# Multi-Channel-Thermocouple-Shield.net
KiCad netlist of a schematic drawn in EAGLE
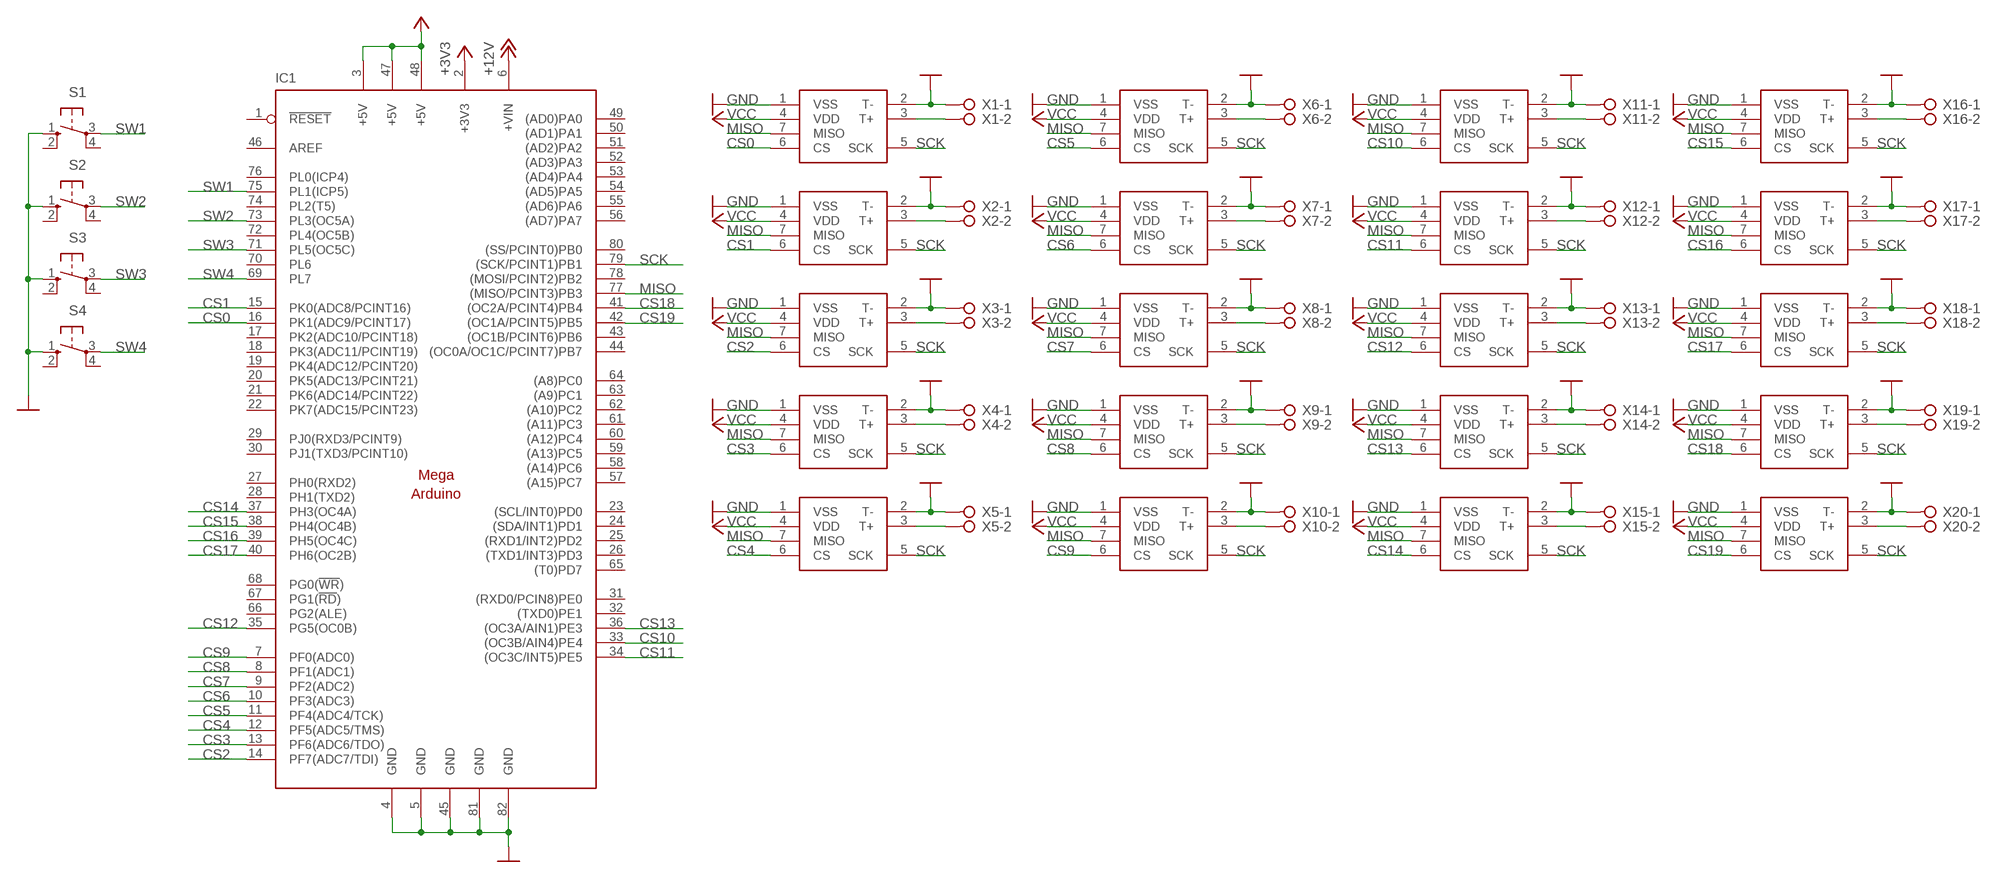
[diagram p0: schematic, sheet 1]

(export (version "E")
  (design (tool "Eeschema 10.0.6"))
  (components
    (comp (ref "IC1")
      (value "ARDUINO_MEGA-SHIELD")
      (footprint "eagle-import:MEGA_ARDUINO")
      (libsource (lib "eagle-import") (part "ARDUINO_MEGA-SHIELD"))
    )
    (comp (ref "S1")
      (value "SW-PUSHBUTTON")
      (footprint "eagle-import:B3F-10XX")
      (fields (field (name "MPN") "B3F-1000"))
      (libsource (lib "eagle-import") (part "SW-PUSHBUTTON"))
    )
    (comp (ref "S2")
      (value "SW-PUSHBUTTON")
      (footprint "eagle-import:B3F-10XX")
      (fields (field (name "MPN") "B3F-1000"))
      (libsource (lib "eagle-import") (part "SW-PUSHBUTTON"))
    )
    (comp (ref "S3")
      (value "SW-PUSHBUTTON")
      (footprint "eagle-import:B3F-10XX")
      (fields (field (name "MPN") "B3F-1000"))
      (libsource (lib "eagle-import") (part "SW-PUSHBUTTON"))
    )
    (comp (ref "S4")
      (value "SW-PUSHBUTTON")
      (footprint "eagle-import:B3F-10XX")
      (fields (field (name "MPN") "B3F-1000"))
      (libsource (lib "eagle-import") (part "SW-PUSHBUTTON"))
    )
    (comp (ref "U$1")
      (value "MAX6675")
      (footprint "eagle-import:SO08")
      (libsource (lib "eagle-import") (part "MAX6675"))
    )
    (comp (ref "U$2")
      (value "MAX6675")
      (footprint "eagle-import:SO08")
      (libsource (lib "eagle-import") (part "MAX6675"))
    )
    (comp (ref "U$3")
      (value "MAX6675")
      (footprint "eagle-import:SO08")
      (libsource (lib "eagle-import") (part "MAX6675"))
    )
    (comp (ref "U$4")
      (value "MAX6675")
      (footprint "eagle-import:SO08")
      (libsource (lib "eagle-import") (part "MAX6675"))
    )
    (comp (ref "U$5")
      (value "MAX6675")
      (footprint "eagle-import:SO08")
      (libsource (lib "eagle-import") (part "MAX6675"))
    )
    (comp (ref "U$6")
      (value "MAX6675")
      (footprint "eagle-import:SO08")
      (libsource (lib "eagle-import") (part "MAX6675"))
    )
    (comp (ref "U$7")
      (value "MAX6675")
      (footprint "eagle-import:SO08")
      (libsource (lib "eagle-import") (part "MAX6675"))
    )
    (comp (ref "U$8")
      (value "MAX6675")
      (footprint "eagle-import:SO08")
      (libsource (lib "eagle-import") (part "MAX6675"))
    )
    (comp (ref "U$9")
      (value "MAX6675")
      (footprint "eagle-import:SO08")
      (libsource (lib "eagle-import") (part "MAX6675"))
    )
    (comp (ref "U$10")
      (value "MAX6675")
      (footprint "eagle-import:SO08")
      (libsource (lib "eagle-import") (part "MAX6675"))
    )
    (comp (ref "U$11")
      (value "MAX6675")
      (footprint "eagle-import:SO08")
      (libsource (lib "eagle-import") (part "MAX6675"))
    )
    (comp (ref "U$12")
      (value "MAX6675")
      (footprint "eagle-import:SO08")
      (libsource (lib "eagle-import") (part "MAX6675"))
    )
    (comp (ref "U$13")
      (value "MAX6675")
      (footprint "eagle-import:SO08")
      (libsource (lib "eagle-import") (part "MAX6675"))
    )
    (comp (ref "U$14")
      (value "MAX6675")
      (footprint "eagle-import:SO08")
      (libsource (lib "eagle-import") (part "MAX6675"))
    )
    (comp (ref "U$15")
      (value "MAX6675")
      (footprint "eagle-import:SO08")
      (libsource (lib "eagle-import") (part "MAX6675"))
    )
    (comp (ref "U$16")
      (value "MAX6675")
      (footprint "eagle-import:SO08")
      (libsource (lib "eagle-import") (part "MAX6675"))
    )
    (comp (ref "U$17")
      (value "MAX6675")
      (footprint "eagle-import:SO08")
      (libsource (lib "eagle-import") (part "MAX6675"))
    )
    (comp (ref "U$18")
      (value "MAX6675")
      (footprint "eagle-import:SO08")
      (libsource (lib "eagle-import") (part "MAX6675"))
    )
    (comp (ref "U$19")
      (value "MAX6675")
      (footprint "eagle-import:SO08")
      (libsource (lib "eagle-import") (part "MAX6675"))
    )
    (comp (ref "U$20")
      (value "MAX6675")
      (footprint "eagle-import:SO08")
      (libsource (lib "eagle-import") (part "MAX6675"))
    )
    (comp (ref "X1")
      (value "W237-02P")
      (footprint "eagle-import:W237-132")
      (libsource (lib "eagle-import") (part "W237-02P"))
    )
    (comp (ref "X2")
      (value "W237-02P")
      (footprint "eagle-import:W237-132")
      (libsource (lib "eagle-import") (part "W237-02P"))
    )
    (comp (ref "X3")
      (value "W237-02P")
      (footprint "eagle-import:W237-132")
      (libsource (lib "eagle-import") (part "W237-02P"))
    )
    (comp (ref "X4")
      (value "W237-02P")
      (footprint "eagle-import:W237-132")
      (libsource (lib "eagle-import") (part "W237-02P"))
    )
    (comp (ref "X5")
      (value "W237-02P")
      (footprint "eagle-import:W237-132")
      (libsource (lib "eagle-import") (part "W237-02P"))
    )
    (comp (ref "X6")
      (value "W237-02P")
      (footprint "eagle-import:W237-132")
      (libsource (lib "eagle-import") (part "W237-02P"))
    )
    (comp (ref "X7")
      (value "W237-02P")
      (footprint "eagle-import:W237-132")
      (libsource (lib "eagle-import") (part "W237-02P"))
    )
    (comp (ref "X8")
      (value "W237-02P")
      (footprint "eagle-import:W237-132")
      (libsource (lib "eagle-import") (part "W237-02P"))
    )
    (comp (ref "X9")
      (value "W237-02P")
      (footprint "eagle-import:W237-132")
      (libsource (lib "eagle-import") (part "W237-02P"))
    )
    (comp (ref "X10")
      (value "W237-02P")
      (footprint "eagle-import:W237-132")
      (libsource (lib "eagle-import") (part "W237-02P"))
    )
    (comp (ref "X11")
      (value "W237-02P")
      (footprint "eagle-import:W237-132")
      (libsource (lib "eagle-import") (part "W237-02P"))
    )
    (comp (ref "X12")
      (value "W237-02P")
      (footprint "eagle-import:W237-132")
      (libsource (lib "eagle-import") (part "W237-02P"))
    )
    (comp (ref "X13")
      (value "W237-02P")
      (footprint "eagle-import:W237-132")
      (libsource (lib "eagle-import") (part "W237-02P"))
    )
    (comp (ref "X14")
      (value "W237-02P")
      (footprint "eagle-import:W237-132")
      (libsource (lib "eagle-import") (part "W237-02P"))
    )
    (comp (ref "X15")
      (value "W237-02P")
      (footprint "eagle-import:W237-132")
      (libsource (lib "eagle-import") (part "W237-02P"))
    )
    (comp (ref "X16")
      (value "W237-02P")
      (footprint "eagle-import:W237-132")
      (libsource (lib "eagle-import") (part "W237-02P"))
    )
    (comp (ref "X17")
      (value "W237-02P")
      (footprint "eagle-import:W237-132")
      (libsource (lib "eagle-import") (part "W237-02P"))
    )
    (comp (ref "X18")
      (value "W237-02P")
      (footprint "eagle-import:W237-132")
      (libsource (lib "eagle-import") (part "W237-02P"))
    )
    (comp (ref "X19")
      (value "W237-02P")
      (footprint "eagle-import:W237-132")
      (libsource (lib "eagle-import") (part "W237-02P"))
    )
    (comp (ref "X20")
      (value "W237-02P")
      (footprint "eagle-import:W237-132")
      (libsource (lib "eagle-import") (part "W237-02P"))
    )
  )
  (nets
    (net (code "1") (name "+3V3") (class "Default")
      (node (ref "IC1") (pin "2") (pinfunction "+3V3_2") (pintype "power_in"))
    )
    (net (code "2") (name "+12V") (class "Default")
      (node (ref "IC1") (pin "6") (pinfunction "+VIN_6") (pintype "power_in"))
    )
    (net (code "3") (name "/CS0") (class "Default")
      (node (ref "IC1") (pin "16") (pinfunction "PK1(ADC9/PCINT17)_16") (pintype "bidirectional"))
      (node (ref "U$1") (pin "6") (pinfunction "CS_6") (pintype "bidirectional"))
    )
    (net (code "4") (name "/CS1") (class "Default")
      (node (ref "IC1") (pin "15") (pinfunction "PK0(ADC8/PCINT16)_15") (pintype "bidirectional"))
      (node (ref "U$2") (pin "6") (pinfunction "CS_6") (pintype "bidirectional"))
    )
    (net (code "5") (name "/CS2") (class "Default")
      (node (ref "IC1") (pin "14") (pinfunction "PF7(ADC7/TDI)_14") (pintype "bidirectional"))
      (node (ref "U$3") (pin "6") (pinfunction "CS_6") (pintype "bidirectional"))
    )
    (net (code "6") (name "/CS3") (class "Default")
      (node (ref "IC1") (pin "13") (pinfunction "PF6(ADC6/TDO)_13") (pintype "bidirectional"))
      (node (ref "U$4") (pin "6") (pinfunction "CS_6") (pintype "bidirectional"))
    )
    (net (code "7") (name "/CS4") (class "Default")
      (node (ref "IC1") (pin "12") (pinfunction "PF5(ADC5/TMS)_12") (pintype "bidirectional"))
      (node (ref "U$5") (pin "6") (pinfunction "CS_6") (pintype "bidirectional"))
    )
    (net (code "8") (name "/CS5") (class "Default")
      (node (ref "IC1") (pin "11") (pinfunction "PF4(ADC4/TCK)_11") (pintype "bidirectional"))
      (node (ref "U$6") (pin "6") (pinfunction "CS_6") (pintype "bidirectional"))
    )
    (net (code "9") (name "/CS6") (class "Default")
      (node (ref "IC1") (pin "10") (pinfunction "PF3(ADC3)_10") (pintype "bidirectional"))
      (node (ref "U$7") (pin "6") (pinfunction "CS_6") (pintype "bidirectional"))
    )
    (net (code "10") (name "/CS7") (class "Default")
      (node (ref "IC1") (pin "9") (pinfunction "PF2(ADC2)_9") (pintype "bidirectional"))
      (node (ref "U$8") (pin "6") (pinfunction "CS_6") (pintype "bidirectional"))
    )
    (net (code "11") (name "/CS8") (class "Default")
      (node (ref "IC1") (pin "8") (pinfunction "PF1(ADC1)_8") (pintype "bidirectional"))
      (node (ref "U$9") (pin "6") (pinfunction "CS_6") (pintype "bidirectional"))
    )
    (net (code "12") (name "/CS9") (class "Default")
      (node (ref "IC1") (pin "7") (pinfunction "PF0(ADC0)_7") (pintype "bidirectional"))
      (node (ref "U$10") (pin "6") (pinfunction "CS_6") (pintype "bidirectional"))
    )
    (net (code "13") (name "/CS10") (class "Default")
      (node (ref "IC1") (pin "33") (pinfunction "(OC3B/AIN4)PE4_33") (pintype "bidirectional"))
      (node (ref "U$11") (pin "6") (pinfunction "CS_6") (pintype "bidirectional"))
    )
    (net (code "14") (name "/CS11") (class "Default")
      (node (ref "IC1") (pin "34") (pinfunction "(OC3C/INT5)PE5_34") (pintype "bidirectional"))
      (node (ref "U$12") (pin "6") (pinfunction "CS_6") (pintype "bidirectional"))
    )
    (net (code "15") (name "/CS12") (class "Default")
      (node (ref "IC1") (pin "35") (pinfunction "PG5(OC0B)_35") (pintype "bidirectional"))
      (node (ref "U$13") (pin "6") (pinfunction "CS_6") (pintype "bidirectional"))
    )
    (net (code "16") (name "/CS13") (class "Default")
      (node (ref "IC1") (pin "36") (pinfunction "(OC3A/AIN1)PE3_36") (pintype "bidirectional"))
      (node (ref "U$14") (pin "6") (pinfunction "CS_6") (pintype "bidirectional"))
    )
    (net (code "17") (name "/CS14") (class "Default")
      (node (ref "IC1") (pin "37") (pinfunction "PH3(OC4A)_37") (pintype "bidirectional"))
      (node (ref "U$15") (pin "6") (pinfunction "CS_6") (pintype "bidirectional"))
    )
    (net (code "18") (name "/CS15") (class "Default")
      (node (ref "IC1") (pin "38") (pinfunction "PH4(OC4B)_38") (pintype "bidirectional"))
      (node (ref "U$16") (pin "6") (pinfunction "CS_6") (pintype "bidirectional"))
    )
    (net (code "19") (name "/CS16") (class "Default")
      (node (ref "IC1") (pin "39") (pinfunction "PH5(OC4C)_39") (pintype "bidirectional"))
      (node (ref "U$17") (pin "6") (pinfunction "CS_6") (pintype "bidirectional"))
    )
    (net (code "20") (name "/CS17") (class "Default")
      (node (ref "IC1") (pin "40") (pinfunction "PH6(OC2B)_40") (pintype "bidirectional"))
      (node (ref "U$18") (pin "6") (pinfunction "CS_6") (pintype "bidirectional"))
    )
    (net (code "21") (name "/CS18") (class "Default")
      (node (ref "IC1") (pin "41") (pinfunction "(OC2A/PCINT4)PB4_41") (pintype "bidirectional"))
      (node (ref "U$19") (pin "6") (pinfunction "CS_6") (pintype "bidirectional"))
    )
    (net (code "22") (name "/CS19") (class "Default")
      (node (ref "IC1") (pin "42") (pinfunction "(OC1A/PCINT5)PB5_42") (pintype "bidirectional"))
      (node (ref "U$20") (pin "6") (pinfunction "CS_6") (pintype "bidirectional"))
    )
    (net (code "23") (name "/MISO") (class "Default")
      (node (ref "IC1") (pin "77") (pinfunction "(MISO/PCINT3)PB3_77") (pintype "bidirectional"))
      (node (ref "U$1") (pin "7") (pinfunction "MISO_7") (pintype "bidirectional"))
      (node (ref "U$10") (pin "7") (pinfunction "MISO_7") (pintype "bidirectional"))
      (node (ref "U$11") (pin "7") (pinfunction "MISO_7") (pintype "bidirectional"))
      (node (ref "U$12") (pin "7") (pinfunction "MISO_7") (pintype "bidirectional"))
      (node (ref "U$13") (pin "7") (pinfunction "MISO_7") (pintype "bidirectional"))
      (node (ref "U$14") (pin "7") (pinfunction "MISO_7") (pintype "bidirectional"))
      (node (ref "U$15") (pin "7") (pinfunction "MISO_7") (pintype "bidirectional"))
      (node (ref "U$16") (pin "7") (pinfunction "MISO_7") (pintype "bidirectional"))
      (node (ref "U$17") (pin "7") (pinfunction "MISO_7") (pintype "bidirectional"))
      (node (ref "U$18") (pin "7") (pinfunction "MISO_7") (pintype "bidirectional"))
      (node (ref "U$19") (pin "7") (pinfunction "MISO_7") (pintype "bidirectional"))
      (node (ref "U$2") (pin "7") (pinfunction "MISO_7") (pintype "bidirectional"))
      (node (ref "U$20") (pin "7") (pinfunction "MISO_7") (pintype "bidirectional"))
      (node (ref "U$3") (pin "7") (pinfunction "MISO_7") (pintype "bidirectional"))
      (node (ref "U$4") (pin "7") (pinfunction "MISO_7") (pintype "bidirectional"))
      (node (ref "U$5") (pin "7") (pinfunction "MISO_7") (pintype "bidirectional"))
      (node (ref "U$6") (pin "7") (pinfunction "MISO_7") (pintype "bidirectional"))
      (node (ref "U$7") (pin "7") (pinfunction "MISO_7") (pintype "bidirectional"))
      (node (ref "U$8") (pin "7") (pinfunction "MISO_7") (pintype "bidirectional"))
      (node (ref "U$9") (pin "7") (pinfunction "MISO_7") (pintype "bidirectional"))
    )
    (net (code "24") (name "/SCK") (class "Default")
      (node (ref "IC1") (pin "79") (pinfunction "(SCK/PCINT1)PB1_79") (pintype "bidirectional"))
      (node (ref "U$1") (pin "5") (pinfunction "SCK_5") (pintype "bidirectional"))
      (node (ref "U$10") (pin "5") (pinfunction "SCK_5") (pintype "bidirectional"))
      (node (ref "U$11") (pin "5") (pinfunction "SCK_5") (pintype "bidirectional"))
      (node (ref "U$12") (pin "5") (pinfunction "SCK_5") (pintype "bidirectional"))
      (node (ref "U$13") (pin "5") (pinfunction "SCK_5") (pintype "bidirectional"))
      (node (ref "U$14") (pin "5") (pinfunction "SCK_5") (pintype "bidirectional"))
      (node (ref "U$15") (pin "5") (pinfunction "SCK_5") (pintype "bidirectional"))
      (node (ref "U$16") (pin "5") (pinfunction "SCK_5") (pintype "bidirectional"))
      (node (ref "U$17") (pin "5") (pinfunction "SCK_5") (pintype "bidirectional"))
      (node (ref "U$18") (pin "5") (pinfunction "SCK_5") (pintype "bidirectional"))
      (node (ref "U$19") (pin "5") (pinfunction "SCK_5") (pintype "bidirectional"))
      (node (ref "U$2") (pin "5") (pinfunction "SCK_5") (pintype "bidirectional"))
      (node (ref "U$20") (pin "5") (pinfunction "SCK_5") (pintype "bidirectional"))
      (node (ref "U$3") (pin "5") (pinfunction "SCK_5") (pintype "bidirectional"))
      (node (ref "U$4") (pin "5") (pinfunction "SCK_5") (pintype "bidirectional"))
      (node (ref "U$5") (pin "5") (pinfunction "SCK_5") (pintype "bidirectional"))
      (node (ref "U$6") (pin "5") (pinfunction "SCK_5") (pintype "bidirectional"))
      (node (ref "U$7") (pin "5") (pinfunction "SCK_5") (pintype "bidirectional"))
      (node (ref "U$8") (pin "5") (pinfunction "SCK_5") (pintype "bidirectional"))
      (node (ref "U$9") (pin "5") (pinfunction "SCK_5") (pintype "bidirectional"))
    )
    (net (code "25") (name "/SW1") (class "Default")
      (node (ref "IC1") (pin "75") (pinfunction "PL1(ICP5)_75") (pintype "bidirectional"))
      (node (ref "S1") (pin "3") (pinfunction "P_3") (pintype "passive"))
    )
    (net (code "26") (name "/SW2") (class "Default")
      (node (ref "IC1") (pin "73") (pinfunction "PL3(OC5A)_73") (pintype "bidirectional"))
      (node (ref "S2") (pin "3") (pinfunction "P_3") (pintype "passive"))
    )
    (net (code "27") (name "/SW3") (class "Default")
      (node (ref "IC1") (pin "71") (pinfunction "PL5(OC5C)_71") (pintype "bidirectional"))
      (node (ref "S3") (pin "3") (pinfunction "P_3") (pintype "passive"))
    )
    (net (code "28") (name "/SW4") (class "Default")
      (node (ref "IC1") (pin "69") (pinfunction "PL7_69") (pintype "bidirectional"))
      (node (ref "S4") (pin "3") (pinfunction "P_3") (pintype "passive"))
    )
    (net (code "29") (name "GND") (class "Default")
      (node (ref "IC1") (pin "4") (pinfunction "GND_4") (pintype "power_in"))
      (node (ref "IC1") (pin "45") (pinfunction "GND_45") (pintype "power_in"))
      (node (ref "IC1") (pin "5") (pinfunction "GND_5") (pintype "power_in"))
      (node (ref "IC1") (pin "81") (pinfunction "GND_81") (pintype "power_in"))
      (node (ref "IC1") (pin "82") (pinfunction "GND_82") (pintype "power_in"))
      (node (ref "S1") (pin "1") (pinfunction "S_1") (pintype "passive"))
      (node (ref "S2") (pin "1") (pinfunction "S_1") (pintype "passive"))
      (node (ref "S3") (pin "1") (pinfunction "S_1") (pintype "passive"))
      (node (ref "S4") (pin "1") (pinfunction "S_1") (pintype "passive"))
      (node (ref "U$1") (pin "1") (pinfunction "VSS_1") (pintype "bidirectional"))
      (node (ref "U$1") (pin "2") (pinfunction "T-_2") (pintype "bidirectional"))
      (node (ref "U$10") (pin "1") (pinfunction "VSS_1") (pintype "bidirectional"))
      (node (ref "U$10") (pin "2") (pinfunction "T-_2") (pintype "bidirectional"))
      (node (ref "U$11") (pin "1") (pinfunction "VSS_1") (pintype "bidirectional"))
      (node (ref "U$11") (pin "2") (pinfunction "T-_2") (pintype "bidirectional"))
      (node (ref "U$12") (pin "1") (pinfunction "VSS_1") (pintype "bidirectional"))
      (node (ref "U$12") (pin "2") (pinfunction "T-_2") (pintype "bidirectional"))
      (node (ref "U$13") (pin "1") (pinfunction "VSS_1") (pintype "bidirectional"))
      (node (ref "U$13") (pin "2") (pinfunction "T-_2") (pintype "bidirectional"))
      (node (ref "U$14") (pin "1") (pinfunction "VSS_1") (pintype "bidirectional"))
      (node (ref "U$14") (pin "2") (pinfunction "T-_2") (pintype "bidirectional"))
      (node (ref "U$15") (pin "1") (pinfunction "VSS_1") (pintype "bidirectional"))
      (node (ref "U$15") (pin "2") (pinfunction "T-_2") (pintype "bidirectional"))
      (node (ref "U$16") (pin "1") (pinfunction "VSS_1") (pintype "bidirectional"))
      (node (ref "U$16") (pin "2") (pinfunction "T-_2") (pintype "bidirectional"))
      (node (ref "U$17") (pin "1") (pinfunction "VSS_1") (pintype "bidirectional"))
      (node (ref "U$17") (pin "2") (pinfunction "T-_2") (pintype "bidirectional"))
      (node (ref "U$18") (pin "1") (pinfunction "VSS_1") (pintype "bidirectional"))
      (node (ref "U$18") (pin "2") (pinfunction "T-_2") (pintype "bidirectional"))
      (node (ref "U$19") (pin "1") (pinfunction "VSS_1") (pintype "bidirectional"))
      (node (ref "U$19") (pin "2") (pinfunction "T-_2") (pintype "bidirectional"))
      (node (ref "U$2") (pin "1") (pinfunction "VSS_1") (pintype "bidirectional"))
      (node (ref "U$2") (pin "2") (pinfunction "T-_2") (pintype "bidirectional"))
      (node (ref "U$20") (pin "1") (pinfunction "VSS_1") (pintype "bidirectional"))
      (node (ref "U$20") (pin "2") (pinfunction "T-_2") (pintype "bidirectional"))
      (node (ref "U$3") (pin "1") (pinfunction "VSS_1") (pintype "bidirectional"))
      (node (ref "U$3") (pin "2") (pinfunction "T-_2") (pintype "bidirectional"))
      (node (ref "U$4") (pin "1") (pinfunction "VSS_1") (pintype "bidirectional"))
      (node (ref "U$4") (pin "2") (pinfunction "T-_2") (pintype "bidirectional"))
      (node (ref "U$5") (pin "1") (pinfunction "VSS_1") (pintype "bidirectional"))
      (node (ref "U$5") (pin "2") (pinfunction "T-_2") (pintype "bidirectional"))
      (node (ref "U$6") (pin "1") (pinfunction "VSS_1") (pintype "bidirectional"))
      (node (ref "U$6") (pin "2") (pinfunction "T-_2") (pintype "bidirectional"))
      (node (ref "U$7") (pin "1") (pinfunction "VSS_1") (pintype "bidirectional"))
      (node (ref "U$7") (pin "2") (pinfunction "T-_2") (pintype "bidirectional"))
      (node (ref "U$8") (pin "1") (pinfunction "VSS_1") (pintype "bidirectional"))
      (node (ref "U$8") (pin "2") (pinfunction "T-_2") (pintype "bidirectional"))
      (node (ref "U$9") (pin "1") (pinfunction "VSS_1") (pintype "bidirectional"))
      (node (ref "U$9") (pin "2") (pinfunction "T-_2") (pintype "bidirectional"))
      (node (ref "X1") (pin "1") (pinfunction "KL_1") (pintype "passive"))
      (node (ref "X10") (pin "1") (pinfunction "KL_1") (pintype "passive"))
      (node (ref "X11") (pin "1") (pinfunction "KL_1") (pintype "passive"))
      (node (ref "X12") (pin "1") (pinfunction "KL_1") (pintype "passive"))
      (node (ref "X13") (pin "1") (pinfunction "KL_1") (pintype "passive"))
      (node (ref "X14") (pin "1") (pinfunction "KL_1") (pintype "passive"))
      (node (ref "X15") (pin "1") (pinfunction "KL_1") (pintype "passive"))
      (node (ref "X16") (pin "1") (pinfunction "KL_1") (pintype "passive"))
      (node (ref "X17") (pin "1") (pinfunction "KL_1") (pintype "passive"))
      (node (ref "X18") (pin "1") (pinfunction "KL_1") (pintype "passive"))
      (node (ref "X19") (pin "1") (pinfunction "KL_1") (pintype "passive"))
      (node (ref "X2") (pin "1") (pinfunction "KL_1") (pintype "passive"))
      (node (ref "X20") (pin "1") (pinfunction "KL_1") (pintype "passive"))
      (node (ref "X3") (pin "1") (pinfunction "KL_1") (pintype "passive"))
      (node (ref "X4") (pin "1") (pinfunction "KL_1") (pintype "passive"))
      (node (ref "X5") (pin "1") (pinfunction "KL_1") (pintype "passive"))
      (node (ref "X6") (pin "1") (pinfunction "KL_1") (pintype "passive"))
      (node (ref "X7") (pin "1") (pinfunction "KL_1") (pintype "passive"))
      (node (ref "X8") (pin "1") (pinfunction "KL_1") (pintype "passive"))
      (node (ref "X9") (pin "1") (pinfunction "KL_1") (pintype "passive"))
    )
    (net (code "30") (name "Net-(U$1-T+)") (class "Default")
      (node (ref "U$1") (pin "3") (pinfunction "T+_3") (pintype "bidirectional"))
      (node (ref "X1") (pin "2") (pinfunction "KL_2") (pintype "passive"))
    )
    (net (code "31") (name "Net-(U$2-T+)") (class "Default")
      (node (ref "U$2") (pin "3") (pinfunction "T+_3") (pintype "bidirectional"))
      (node (ref "X2") (pin "2") (pinfunction "KL_2") (pintype "passive"))
    )
    (net (code "32") (name "Net-(U$3-T+)") (class "Default")
      (node (ref "U$3") (pin "3") (pinfunction "T+_3") (pintype "bidirectional"))
      (node (ref "X3") (pin "2") (pinfunction "KL_2") (pintype "passive"))
    )
    (net (code "33") (name "Net-(U$4-T+)") (class "Default")
      (node (ref "U$4") (pin "3") (pinfunction "T+_3") (pintype "bidirectional"))
      (node (ref "X4") (pin "2") (pinfunction "KL_2") (pintype "passive"))
    )
    (net (code "34") (name "Net-(U$5-T+)") (class "Default")
      (node (ref "U$5") (pin "3") (pinfunction "T+_3") (pintype "bidirectional"))
      (node (ref "X5") (pin "2") (pinfunction "KL_2") (pintype "passive"))
    )
    (net (code "35") (name "Net-(U$6-T+)") (class "Default")
      (node (ref "U$6") (pin "3") (pinfunction "T+_3") (pintype "bidirectional"))
      (node (ref "X6") (pin "2") (pinfunction "KL_2") (pintype "passive"))
    )
    (net (code "36") (name "Net-(U$7-T+)") (class "Default")
      (node (ref "U$7") (pin "3") (pinfunction "T+_3") (pintype "bidirectional"))
      (node (ref "X7") (pin "2") (pinfunction "KL_2") (pintype "passive"))
    )
    (net (code "37") (name "Net-(U$8-T+)") (class "Default")
      (node (ref "U$8") (pin "3") (pinfunction "T+_3") (pintype "bidirectional"))
      (node (ref "X8") (pin "2") (pinfunction "KL_2") (pintype "passive"))
    )
    (net (code "38") (name "Net-(U$9-T+)") (class "Default")
      (node (ref "U$9") (pin "3") (pinfunction "T+_3") (pintype "bidirectional"))
      (node (ref "X9") (pin "2") (pinfunction "KL_2") (pintype "passive"))
    )
    (net (code "39") (name "Net-(U$10-T+)") (class "Default")
      (node (ref "U$10") (pin "3") (pinfunction "T+_3") (pintype "bidirectional"))
      (node (ref "X10") (pin "2") (pinfunction "KL_2") (pintype "passive"))
    )
    (net (code "40") (name "Net-(U$11-T+)") (class "Default")
      (node (ref "U$11") (pin "3") (pinfunction "T+_3") (pintype "bidirectional"))
      (node (ref "X11") (pin "2") (pinfunction "KL_2") (pintype "passive"))
    )
    (net (code "41") (name "Net-(U$12-T+)") (class "Default")
      (node (ref "U$12") (pin "3") (pinfunction "T+_3") (pintype "bidirectional"))
      (node (ref "X12") (pin "2") (pinfunction "KL_2") (pintype "passive"))
    )
    (net (code "42") (name "Net-(U$13-T+)") (class "Default")
      (node (ref "U$13") (pin "3") (pinfunction "T+_3") (pintype "bidirectional"))
      (node (ref "X13") (pin "2") (pinfunction "KL_2") (pintype "passive"))
    )
    (net (code "43") (name "Net-(U$14-T+)") (class "Default")
      (node (ref "U$14") (pin "3") (pinfunction "T+_3") (pintype "bidirectional"))
      (node (ref "X14") (pin "2") (pinfunction "KL_2") (pintype "passive"))
    )
    (net (code "44") (name "Net-(U$15-T+)") (class "Default")
      (node (ref "U$15") (pin "3") (pinfunction "T+_3") (pintype "bidirectional"))
      (node (ref "X15") (pin "2") (pinfunction "KL_2") (pintype "passive"))
    )
    (net (code "45") (name "Net-(U$16-T+)") (class "Default")
      (node (ref "U$16") (pin "3") (pinfunction "T+_3") (pintype "bidirectional"))
      (node (ref "X16") (pin "2") (pinfunction "KL_2") (pintype "passive"))
    )
    (net (code "46") (name "Net-(U$17-T+)") (class "Default")
      (node (ref "U$17") (pin "3") (pinfunction "T+_3") (pintype "bidirectional"))
      (node (ref "X17") (pin "2") (pinfunction "KL_2") (pintype "passive"))
    )
    (net (code "47") (name "Net-(U$18-T+)") (class "Default")
      (node (ref "U$18") (pin "3") (pinfunction "T+_3") (pintype "bidirectional"))
      (node (ref "X18") (pin "2") (pinfunction "KL_2") (pintype "passive"))
    )
    (net (code "48") (name "Net-(U$19-T+)") (class "Default")
      (node (ref "U$19") (pin "3") (pinfunction "T+_3") (pintype "bidirectional"))
      (node (ref "X19") (pin "2") (pinfunction "KL_2") (pintype "passive"))
    )
    (net (code "49") (name "Net-(U$20-T+)") (class "Default")
      (node (ref "U$20") (pin "3") (pinfunction "T+_3") (pintype "bidirectional"))
      (node (ref "X20") (pin "2") (pinfunction "KL_2") (pintype "passive"))
    )
    (net (code "50") (name "VCC") (class "Default")
      (node (ref "IC1") (pin "3") (pinfunction "+5V_3") (pintype "power_in"))
      (node (ref "IC1") (pin "47") (pinfunction "+5V_47") (pintype "power_in"))
      (node (ref "IC1") (pin "48") (pinfunction "+5V_48") (pintype "power_in"))
      (node (ref "U$1") (pin "4") (pinfunction "VDD_4") (pintype "bidirectional"))
      (node (ref "U$10") (pin "4") (pinfunction "VDD_4") (pintype "bidirectional"))
      (node (ref "U$11") (pin "4") (pinfunction "VDD_4") (pintype "bidirectional"))
      (node (ref "U$12") (pin "4") (pinfunction "VDD_4") (pintype "bidirectional"))
      (node (ref "U$13") (pin "4") (pinfunction "VDD_4") (pintype "bidirectional"))
      (node (ref "U$14") (pin "4") (pinfunction "VDD_4") (pintype "bidirectional"))
      (node (ref "U$15") (pin "4") (pinfunction "VDD_4") (pintype "bidirectional"))
      (node (ref "U$16") (pin "4") (pinfunction "VDD_4") (pintype "bidirectional"))
      (node (ref "U$17") (pin "4") (pinfunction "VDD_4") (pintype "bidirectional"))
      (node (ref "U$18") (pin "4") (pinfunction "VDD_4") (pintype "bidirectional"))
      (node (ref "U$19") (pin "4") (pinfunction "VDD_4") (pintype "bidirectional"))
      (node (ref "U$2") (pin "4") (pinfunction "VDD_4") (pintype "bidirectional"))
      (node (ref "U$20") (pin "4") (pinfunction "VDD_4") (pintype "bidirectional"))
      (node (ref "U$3") (pin "4") (pinfunction "VDD_4") (pintype "bidirectional"))
      (node (ref "U$4") (pin "4") (pinfunction "VDD_4") (pintype "bidirectional"))
      (node (ref "U$5") (pin "4") (pinfunction "VDD_4") (pintype "bidirectional"))
      (node (ref "U$6") (pin "4") (pinfunction "VDD_4") (pintype "bidirectional"))
      (node (ref "U$7") (pin "4") (pinfunction "VDD_4") (pintype "bidirectional"))
      (node (ref "U$8") (pin "4") (pinfunction "VDD_4") (pintype "bidirectional"))
      (node (ref "U$9") (pin "4") (pinfunction "VDD_4") (pintype "bidirectional"))
    )
    (net (code "51") (name "unconnected-(IC1-(A8)PC0-Pad64)") (class "Default")
      (node (ref "IC1") (pin "64") (pinfunction "(A8)PC0_64") (pintype "bidirectional"))
    )
    (net (code "52") (name "unconnected-(IC1-(A9)PC1-Pad63)") (class "Default")
      (node (ref "IC1") (pin "63") (pinfunction "(A9)PC1_63") (pintype "bidirectional"))
    )
    (net (code "53") (name "unconnected-(IC1-(A10)PC2-Pad62)") (class "Default")
      (node (ref "IC1") (pin "62") (pinfunction "(A10)PC2_62") (pintype "bidirectional"))
    )
    (net (code "54") (name "unconnected-(IC1-(A11)PC3-Pad61)") (class "Default")
      (node (ref "IC1") (pin "61") (pinfunction "(A11)PC3_61") (pintype "bidirectional"))
    )
    (net (code "55") (name "unconnected-(IC1-(A12)PC4-Pad60)") (class "Default")
      (node (ref "IC1") (pin "60") (pinfunction "(A12)PC4_60") (pintype "bidirectional"))
    )
    (net (code "56") (name "unconnected-(IC1-(A13)PC5-Pad59)") (class "Default")
      (node (ref "IC1") (pin "59") (pinfunction "(A13)PC5_59") (pintype "bidirectional"))
    )
    (net (code "57") (name "unconnected-(IC1-(A14)PC6-Pad58)") (class "Default")
      (node (ref "IC1") (pin "58") (pinfunction "(A14)PC6_58") (pintype "bidirectional"))
    )
    (net (code "58") (name "unconnected-(IC1-(A15)PC7-Pad57)") (class "Default")
      (node (ref "IC1") (pin "57") (pinfunction "(A15)PC7_57") (pintype "bidirectional"))
    )
    (net (code "59") (name "unconnected-(IC1-(AD0)PA0-Pad49)") (class "Default")
      (node (ref "IC1") (pin "49") (pinfunction "(AD0)PA0_49") (pintype "bidirectional"))
    )
    (net (code "60") (name "unconnected-(IC1-(AD1)PA1-Pad50)") (class "Default")
      (node (ref "IC1") (pin "50") (pinfunction "(AD1)PA1_50") (pintype "bidirectional"))
    )
    (net (code "61") (name "unconnected-(IC1-(AD2)PA2-Pad51)") (class "Default")
      (node (ref "IC1") (pin "51") (pinfunction "(AD2)PA2_51") (pintype "bidirectional"))
    )
    (net (code "62") (name "unconnected-(IC1-(AD3)PA3-Pad52)") (class "Default")
      (node (ref "IC1") (pin "52") (pinfunction "(AD3)PA3_52") (pintype "bidirectional"))
    )
    (net (code "63") (name "unconnected-(IC1-(AD4)PA4-Pad53)") (class "Default")
      (node (ref "IC1") (pin "53") (pinfunction "(AD4)PA4_53") (pintype "bidirectional"))
    )
    (net (code "64") (name "unconnected-(IC1-(AD5)PA5-Pad54)") (class "Default")
      (node (ref "IC1") (pin "54") (pinfunction "(AD5)PA5_54") (pintype "bidirectional"))
    )
    (net (code "65") (name "unconnected-(IC1-(AD6)PA6-Pad55)") (class "Default")
      (node (ref "IC1") (pin "55") (pinfunction "(AD6)PA6_55") (pintype "bidirectional"))
    )
    (net (code "66") (name "unconnected-(IC1-(AD7)PA7-Pad56)") (class "Default")
      (node (ref "IC1") (pin "56") (pinfunction "(AD7)PA7_56") (pintype "bidirectional"))
    )
    (net (code "67") (name "unconnected-(IC1-(MOSI{slash}PCINT2)PB2-Pad78)") (class "Default")
      (node (ref "IC1") (pin "78") (pinfunction "(MOSI/PCINT2)PB2_78") (pintype "bidirectional"))
    )
    (net (code "68") (name "unconnected-(IC1-(OC0A{slash}OC1C{slash}PCINT7)PB7-Pad44)") (class "Default")
      (node (ref "IC1") (pin "44") (pinfunction "(OC0A/OC1C/PCINT7)PB7_44") (pintype "bidirectional"))
    )
    (net (code "69") (name "unconnected-(IC1-(OC1B{slash}PCINT6)PB6-Pad43)") (class "Default")
      (node (ref "IC1") (pin "43") (pinfunction "(OC1B/PCINT6)PB6_43") (pintype "bidirectional"))
    )
    (net (code "70") (name "unconnected-(IC1-(RXD0{slash}PCIN8)PE0-Pad31)") (class "Default")
      (node (ref "IC1") (pin "31") (pinfunction "(RXD0/PCIN8)PE0_31") (pintype "bidirectional"))
    )
    (net (code "71") (name "unconnected-(IC1-(RXD1{slash}INT2)PD2-Pad25)") (class "Default")
      (node (ref "IC1") (pin "25") (pinfunction "(RXD1/INT2)PD2_25") (pintype "bidirectional"))
    )
    (net (code "72") (name "unconnected-(IC1-(SCL{slash}INT0)PD0-Pad23)") (class "Default")
      (node (ref "IC1") (pin "23") (pinfunction "(SCL/INT0)PD0_23") (pintype "bidirectional"))
    )
    (net (code "73") (name "unconnected-(IC1-(SDA{slash}INT1)PD1-Pad24)") (class "Default")
      (node (ref "IC1") (pin "24") (pinfunction "(SDA/INT1)PD1_24") (pintype "bidirectional"))
    )
    (net (code "74") (name "unconnected-(IC1-(SS{slash}PCINT0)PB0-Pad80)") (class "Default")
      (node (ref "IC1") (pin "80") (pinfunction "(SS/PCINT0)PB0_80") (pintype "bidirectional"))
    )
    (net (code "75") (name "unconnected-(IC1-(T0)PD7-Pad65)") (class "Default")
      (node (ref "IC1") (pin "65") (pinfunction "(T0)PD7_65") (pintype "bidirectional"))
    )
    (net (code "76") (name "unconnected-(IC1-(TXD0)PE1-Pad32)") (class "Default")
      (node (ref "IC1") (pin "32") (pinfunction "(TXD0)PE1_32") (pintype "bidirectional"))
    )
    (net (code "77") (name "unconnected-(IC1-(TXD1{slash}INT3)PD3-Pad26)") (class "Default")
      (node (ref "IC1") (pin "26") (pinfunction "(TXD1/INT3)PD3_26") (pintype "bidirectional"))
    )
    (net (code "78") (name "unconnected-(IC1-AREF-Pad46)") (class "Default")
      (node (ref "IC1") (pin "46") (pinfunction "AREF_46") (pintype "bidirectional"))
    )
    (net (code "79") (name "unconnected-(IC1-PG0(~{WR})-Pad68)") (class "Default")
      (node (ref "IC1") (pin "68") (pinfunction "PG0(~{WR})_68") (pintype "bidirectional"))
    )
    (net (code "80") (name "unconnected-(IC1-PG1(~{RD})-Pad67)") (class "Default")
      (node (ref "IC1") (pin "67") (pinfunction "PG1(~{RD})_67") (pintype "bidirectional"))
    )
    (net (code "81") (name "unconnected-(IC1-PG2(ALE)-Pad66)") (class "Default")
      (node (ref "IC1") (pin "66") (pinfunction "PG2(ALE)_66") (pintype "bidirectional"))
    )
    (net (code "82") (name "unconnected-(IC1-PH0(RXD2)-Pad27)") (class "Default")
      (node (ref "IC1") (pin "27") (pinfunction "PH0(RXD2)_27") (pintype "bidirectional"))
    )
    (net (code "83") (name "unconnected-(IC1-PH1(TXD2)-Pad28)") (class "Default")
      (node (ref "IC1") (pin "28") (pinfunction "PH1(TXD2)_28") (pintype "bidirectional"))
    )
    (net (code "84") (name "unconnected-(IC1-PJ0(RXD3{slash}PCINT9)-Pad29)") (class "Default")
      (node (ref "IC1") (pin "29") (pinfunction "PJ0(RXD3/PCINT9)_29") (pintype "bidirectional"))
    )
    (net (code "85") (name "unconnected-(IC1-PJ1(TXD3{slash}PCINT10)-Pad30)") (class "Default")
      (node (ref "IC1") (pin "30") (pinfunction "PJ1(TXD3/PCINT10)_30") (pintype "bidirectional"))
    )
    (net (code "86") (name "unconnected-(IC1-PK2(ADC10{slash}PCINT18)-Pad17)") (class "Default")
      (node (ref "IC1") (pin "17") (pinfunction "PK2(ADC10/PCINT18)_17") (pintype "bidirectional"))
    )
    (net (code "87") (name "unconnected-(IC1-PK3(ADC11{slash}PCINT19)-Pad18)") (class "Default")
      (node (ref "IC1") (pin "18") (pinfunction "PK3(ADC11/PCINT19)_18") (pintype "bidirectional"))
    )
    (net (code "88") (name "unconnected-(IC1-PK4(ADC12{slash}PCINT20)-Pad19)") (class "Default")
      (node (ref "IC1") (pin "19") (pinfunction "PK4(ADC12/PCINT20)_19") (pintype "bidirectional"))
    )
    (net (code "89") (name "unconnected-(IC1-PK5(ADC13{slash}PCINT21)-Pad20)") (class "Default")
      (node (ref "IC1") (pin "20") (pinfunction "PK5(ADC13/PCINT21)_20") (pintype "bidirectional"))
    )
    (net (code "90") (name "unconnected-(IC1-PK6(ADC14{slash}PCINT22)-Pad21)") (class "Default")
      (node (ref "IC1") (pin "21") (pinfunction "PK6(ADC14/PCINT22)_21") (pintype "bidirectional"))
    )
    (net (code "91") (name "unconnected-(IC1-PK7(ADC15{slash}PCINT23)-Pad22)") (class "Default")
      (node (ref "IC1") (pin "22") (pinfunction "PK7(ADC15/PCINT23)_22") (pintype "bidirectional"))
    )
    (net (code "92") (name "unconnected-(IC1-PL0(ICP4)-Pad76)") (class "Default")
      (node (ref "IC1") (pin "76") (pinfunction "PL0(ICP4)_76") (pintype "bidirectional"))
    )
    (net (code "93") (name "unconnected-(IC1-PL2(T5)-Pad74)") (class "Default")
      (node (ref "IC1") (pin "74") (pinfunction "PL2(T5)_74") (pintype "bidirectional"))
    )
    (net (code "94") (name "unconnected-(IC1-PL4(OC5B)-Pad72)") (class "Default")
      (node (ref "IC1") (pin "72") (pinfunction "PL4(OC5B)_72") (pintype "bidirectional"))
    )
    (net (code "95") (name "unconnected-(IC1-PL6-Pad70)") (class "Default")
      (node (ref "IC1") (pin "70") (pinfunction "PL6_70") (pintype "bidirectional"))
    )
    (net (code "96") (name "unconnected-(IC1-~{RESET}-Pad1)") (class "Default")
      (node (ref "IC1") (pin "1") (pinfunction "~{RESET}_1") (pintype "bidirectional"))
    )
    (net (code "97") (name "unconnected-(S1-P1-Pad4)") (class "Default")
      (node (ref "S1") (pin "4") (pinfunction "P1_4") (pintype "passive"))
    )
    (net (code "98") (name "unconnected-(S1-S1-Pad2)") (class "Default")
      (node (ref "S1") (pin "2") (pinfunction "S1_2") (pintype "passive"))
    )
    (net (code "99") (name "unconnected-(S2-P1-Pad4)") (class "Default")
      (node (ref "S2") (pin "4") (pinfunction "P1_4") (pintype "passive"))
    )
    (net (code "100") (name "unconnected-(S2-S1-Pad2)") (class "Default")
      (node (ref "S2") (pin "2") (pinfunction "S1_2") (pintype "passive"))
    )
    (net (code "101") (name "unconnected-(S3-P1-Pad4)") (class "Default")
      (node (ref "S3") (pin "4") (pinfunction "P1_4") (pintype "passive"))
    )
    (net (code "102") (name "unconnected-(S3-S1-Pad2)") (class "Default")
      (node (ref "S3") (pin "2") (pinfunction "S1_2") (pintype "passive"))
    )
    (net (code "103") (name "unconnected-(S4-P1-Pad4)") (class "Default")
      (node (ref "S4") (pin "4") (pinfunction "P1_4") (pintype "passive"))
    )
    (net (code "104") (name "unconnected-(S4-S1-Pad2)") (class "Default")
      (node (ref "S4") (pin "2") (pinfunction "S1_2") (pintype "passive"))
    )
  )
)
